# door_FM_rev_A.net
KiCad netlist of a schematic drawn in EAGLE
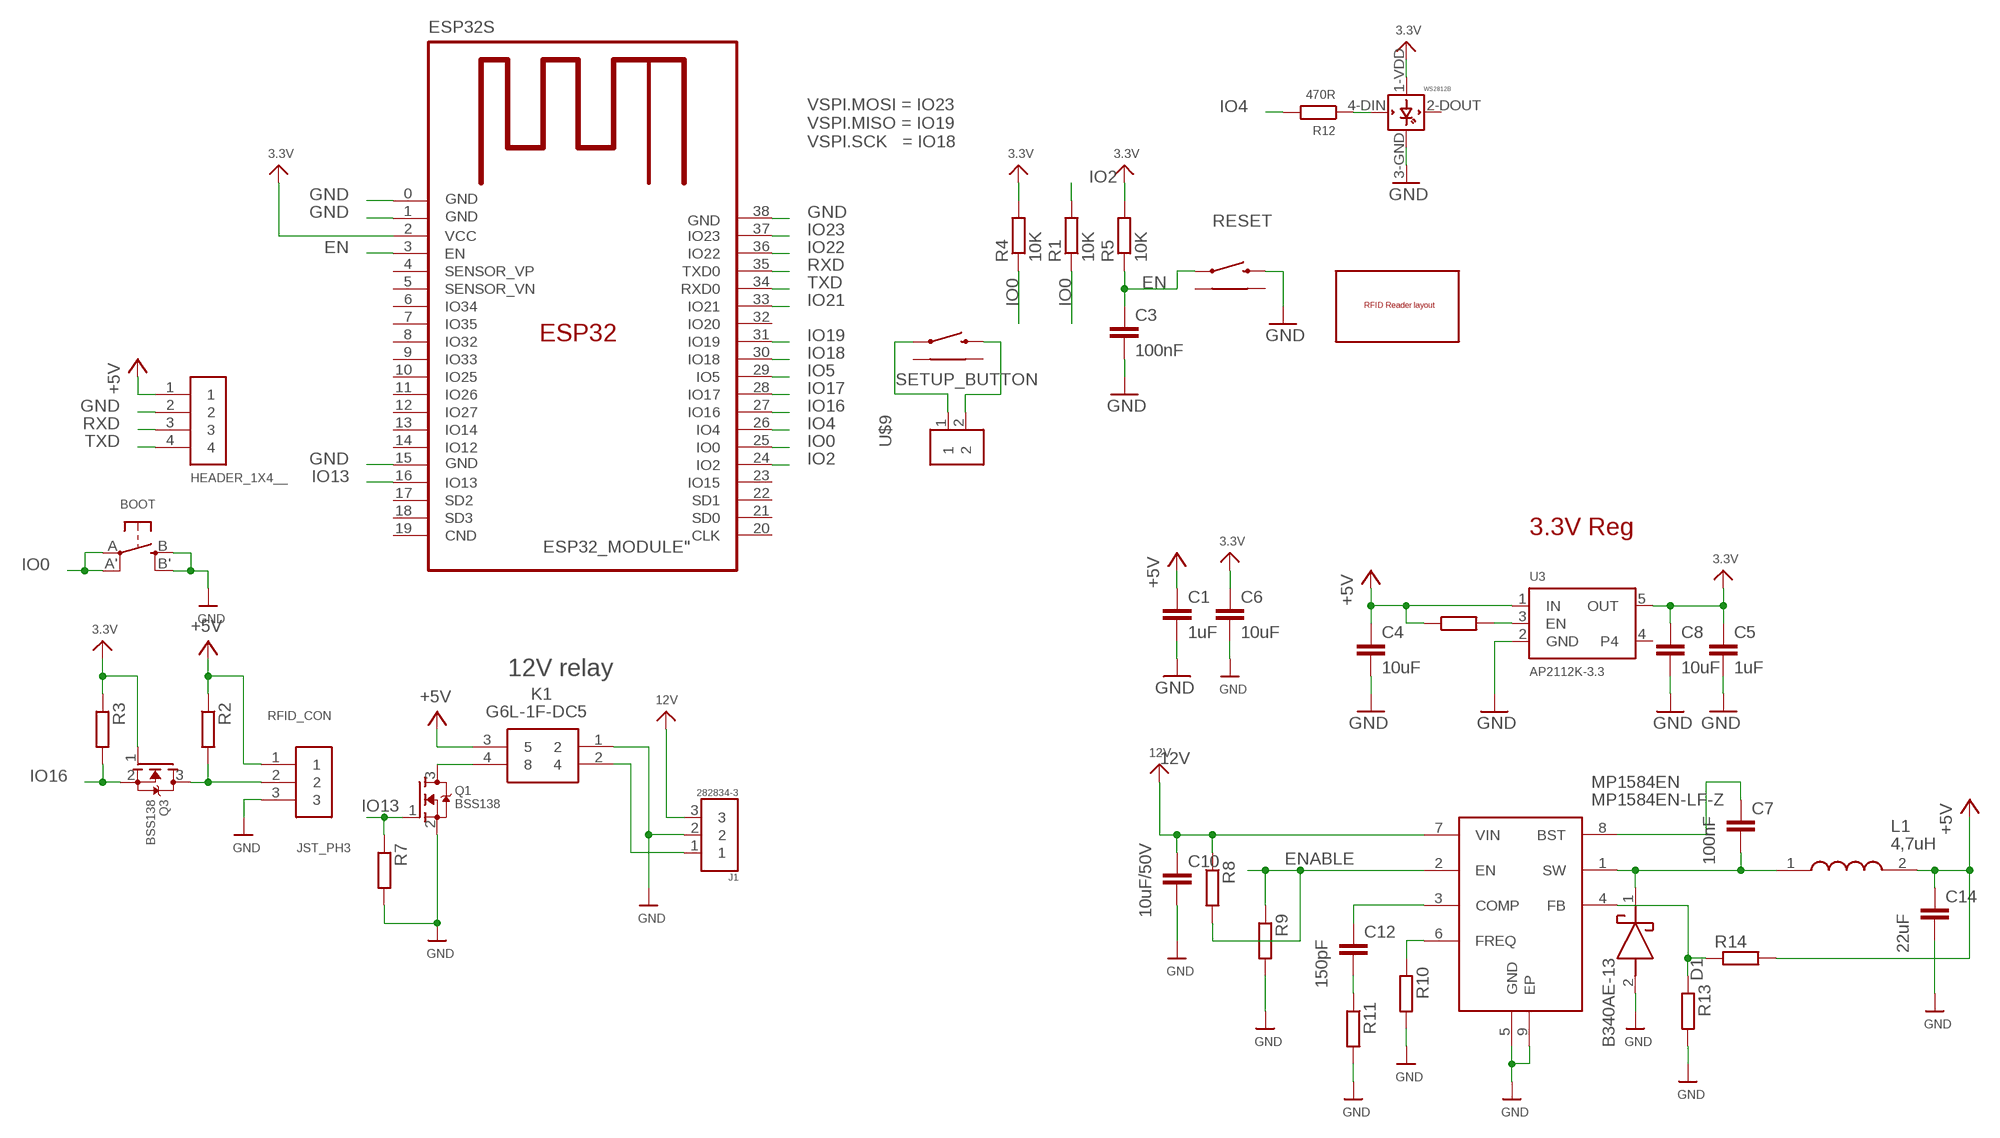
[diagram p0: schematic, sheet 1]

(export (version "E")
  (design (tool "Eeschema 10.0.6"))
  (components
    (comp (ref "BOOT")
      (value "BUTTON_KMR2_4.6X2.8")
      (footprint "eagle-import:BUTTON_KMR2_4.6X2.8")
      (libsource (lib "eagle-import") (part "BUTTON_KMR2_4.6X2.8"))
    )
    (comp (ref "C1")
      (value "1uF")
      (footprint "eagle-import:C0805")
      (libsource (lib "eagle-import") (part "C-EUC0805"))
    )
    (comp (ref "C3")
      (value "100nF")
      (footprint "eagle-import:C0805")
      (libsource (lib "eagle-import") (part "C-EUC0805"))
    )
    (comp (ref "C4")
      (value "10uF")
      (footprint "eagle-import:C0805")
      (libsource (lib "eagle-import") (part "C-EUC0805"))
    )
    (comp (ref "C5")
      (value "1uF")
      (footprint "eagle-import:C0805")
      (libsource (lib "eagle-import") (part "C-EUC0805"))
    )
    (comp (ref "C6")
      (value "10uF")
      (footprint "eagle-import:C0805")
      (libsource (lib "eagle-import") (part "C-EUC0805"))
    )
    (comp (ref "C7")
      (value "100nF")
      (footprint "eagle-import:C0805")
      (libsource (lib "eagle-import") (part "C-EUC0805"))
    )
    (comp (ref "C8")
      (value "10uF")
      (footprint "eagle-import:C0805")
      (libsource (lib "eagle-import") (part "C-EUC0805"))
    )
    (comp (ref "C10")
      (value "10uF/50V")
      (footprint "eagle-import:C0805")
      (libsource (lib "eagle-import") (part "C-EUC0805"))
    )
    (comp (ref "C12")
      (value "150pF")
      (footprint "eagle-import:C0805")
      (libsource (lib "eagle-import") (part "C-EUC0805"))
    )
    (comp (ref "C14")
      (value "22uF")
      (footprint "eagle-import:C0805")
      (libsource (lib "eagle-import") (part "C-EUC0805"))
    )
    (comp (ref "CN1")
      (value "HEADER_1X4__")
      (footprint "eagle-import:HEADER_1X4_RIGHT_ANGLE")
      (libsource (lib "eagle-import") (part "HEADER_1X4__"))
    )
    (comp (ref "D1")
      (value "B340AE-13")
      (footprint "eagle-import:DIOM5226X240N")
      (fields (field (name "MOUSER_PART_NUMBER") "621-B340AE-13"))
      (libsource (lib "eagle-import") (part "B340AE-13"))
    )
    (comp (ref "ESP32S")
      (value "ESP32_MODULE\"")
      (footprint "eagle-import:ESP32_MODULE")
      (libsource (lib "eagle-import") (part "ESP32_MODULE{dblquote}"))
    )
    (comp (ref "J1")
      (value "282834-3")
      (footprint "eagle-import:TE_282834-3")
      (fields (field (name "MF") "TE Connectivity"))
      (libsource (lib "eagle-import") (part "282834-3"))
    )
    (comp (ref "K1")
      (value "G6L-1F-DC5")
      (footprint "eagle-import:G6L-1F-DC5")
      (fields (field (name "MOUSER_PART_NUMBER") "653-G6L-1F-DC5"))
      (libsource (lib "eagle-import") (part "G6L-1F-DC5"))
    )
    (comp (ref "L1")
      (value "4,7uH")
      (footprint "eagle-import:ASPI-0630LR")
      (fields
        (field (name "MANUFACTURER_PART_NUMBER") "ASPI-0630LR-4R7M-T15")
        (field (name "MOUSER_PART_NUMBER") "815-ASPI0630LR4R7T15")
      )
      (libsource (lib "eagle-import") (part "ASPI-0630LR-4R7M-T15"))
    )
    (comp (ref "MP1584EN")
      (value "MP1584EN-LF-Z")
      (footprint "eagle-import:SOIC127P600X170-9N")
      (fields (field (name "MOUSER_PART_NUMBER") "946-MP1584ENLFZ"))
      (libsource (lib "eagle-import") (part "MP1584EN-LF-Z"))
    )
    (comp (ref "Q1")
      (value "BSS138")
      (footprint "eagle-import:SOT95P240X110-3")
      (libsource (lib "eagle-import") (part "MOSFET_N_"))
    )
    (comp (ref "Q3")
      (value "BSS138")
      (footprint "eagle-import:SOT95P240X110-3")
      (libsource (lib "eagle-import") (part "MOSFET_N_"))
    )
    (comp (ref "R1")
      (value "10K")
      (footprint "eagle-import:R0805")
      (libsource (lib "eagle-import") (part "R-EU_R0805"))
    )
    (comp (ref "R2")
      (value "10K")
      (footprint "eagle-import:R0805")
      (libsource (lib "eagle-import") (part "R-EU_R0805"))
    )
    (comp (ref "R3")
      (value "10K")
      (footprint "eagle-import:R0805")
      (libsource (lib "eagle-import") (part "R-EU_R0805"))
    )
    (comp (ref "R4")
      (value "10K")
      (footprint "eagle-import:R0805")
      (libsource (lib "eagle-import") (part "R-EU_R0805"))
    )
    (comp (ref "R5")
      (value "10K")
      (footprint "eagle-import:R0805")
      (libsource (lib "eagle-import") (part "R-EU_R0805"))
    )
    (comp (ref "R7")
      (value "10K")
      (footprint "eagle-import:R0805")
      (libsource (lib "eagle-import") (part "R-EU_R0805"))
    )
    (comp (ref "R8")
      (value "100K")
      (footprint "eagle-import:R0805")
      (libsource (lib "eagle-import") (part "R-EU_R0805"))
    )
    (comp (ref "R9")
      (value "24,9K")
      (footprint "eagle-import:R0805")
      (libsource (lib "eagle-import") (part "R-EU_R0805"))
    )
    (comp (ref "R10")
      (value "100K")
      (footprint "eagle-import:R0805")
      (libsource (lib "eagle-import") (part "R-EU_R0805"))
    )
    (comp (ref "R11")
      (value "100K")
      (footprint "eagle-import:R0805")
      (libsource (lib "eagle-import") (part "R-EU_R0805"))
    )
    (comp (ref "R12")
      (value "470R")
      (footprint "eagle-import:R0805")
      (libsource (lib "eagle-import") (part "R-EU_R0805"))
    )
    (comp (ref "R13")
      (value "40,2K")
      (footprint "eagle-import:R0805")
      (libsource (lib "eagle-import") (part "R-EU_R0805"))
    )
    (comp (ref "R14")
      (value "210K")
      (footprint "eagle-import:R0805")
      (libsource (lib "eagle-import") (part "R-EU_R0805"))
    )
    (comp (ref "R19")
      (value "10K")
      (footprint "eagle-import:R0805")
      (libsource (lib "eagle-import") (part "R-EU_R0805"))
    )
    (comp (ref "RESET")
      (value "TACTILE_SWITCH_RIGHT_ANGLE_THT_")
      (footprint "eagle-import:TACTILE_SWITCH_RIGHT_ANGLE_THT")
      (libsource (lib "eagle-import") (part "TACTILE_SWITCH_RIGHT_ANGLE_THT_"))
    )
    (comp (ref "RFID_CON")
      (value "JST_PH3")
      (footprint "eagle-import:JST-PH3")
      (libsource (lib "eagle-import") (part "JST_PH3"))
    )
    (comp (ref "SETUP_BUTTON")
      (value "TACTILE_SWITCH_RIGHT_ANGLE_THT_")
      (footprint "eagle-import:TACTILE_SWITCH_RIGHT_ANGLE_THT")
      (libsource (lib "eagle-import") (part "TACTILE_SWITCH_RIGHT_ANGLE_THT_"))
    )
    (comp (ref "U$9")
      (value "282834-2")
      (footprint "eagle-import:CONN_282834-2")
      (fields (field (name "MF") "TE Connectivity"))
      (libsource (lib "eagle-import") (part "282834-2"))
    )
    (comp (ref "U$10")
      (value "RFID_READER")
      (footprint "eagle-import:RFID_READER")
      (libsource (lib "eagle-import") (part "RFID_READER"))
    )
    (comp (ref "U3")
      (value "AP2112K-3.3")
      (footprint "eagle-import:SOT95P290X120-5")
      (libsource (lib "eagle-import") (part "AP2112K-3.3_"))
    )
    (comp (ref "WS2812B")
      (value "WS2812B__")
      (footprint "eagle-import:WS2812B_5050")
      (libsource (lib "eagle-import") (part "WS2812B__"))
    )
  )
  (nets
    (net (code "1") (name "+5V") (class "Default")
      (node (ref "C1") (pin "1") (pinfunction "1_1") (pintype "passive"))
      (node (ref "C14") (pin "1") (pinfunction "1_1") (pintype "passive"))
      (node (ref "C4") (pin "1") (pinfunction "1_1") (pintype "passive"))
      (node (ref "CN1") (pin "1") (pinfunction "1_1") (pintype "bidirectional"))
      (node (ref "K1") (pin "3") (pinfunction "5_3") (pintype "bidirectional"))
      (node (ref "L1") (pin "2") (pinfunction "2_2") (pintype "bidirectional"))
      (node (ref "R14") (pin "2") (pinfunction "2_2") (pintype "passive"))
      (node (ref "R19") (pin "1") (pinfunction "1_1") (pintype "passive"))
      (node (ref "R2") (pin "1") (pinfunction "1_1") (pintype "passive"))
      (node (ref "RFID_CON") (pin "1") (pinfunction "1_1") (pintype "bidirectional"))
      (node (ref "U3") (pin "1") (pinfunction "IN_1") (pintype "bidirectional"))
    )
    (net (code "2") (name "/EN") (class "Default")
      (node (ref "C3") (pin "1") (pinfunction "1_1") (pintype "passive"))
      (node (ref "ESP32S") (pin "3") (pinfunction "EN_3") (pintype "bidirectional"))
      (node (ref "R5") (pin "1") (pinfunction "1_1") (pintype "passive"))
      (node (ref "RESET") (pin "1") (pinfunction "1_1") (pintype "passive"))
    )
    (net (code "3") (name "/ENABLE") (class "Default")
      (node (ref "MP1584EN") (pin "2") (pinfunction "EN_2") (pintype "input"))
      (node (ref "R8") (pin "2") (pinfunction "2_2") (pintype "passive"))
      (node (ref "R9") (pin "1") (pinfunction "1_1") (pintype "passive"))
    )
    (net (code "4") (name "/IO0") (class "Default")
      (node (ref "BOOT") (pin "A") (pinfunction "P_A") (pintype "passive"))
      (node (ref "BOOT") (pin "A'") (pinfunction "P1_A'") (pintype "passive"))
      (node (ref "ESP32S") (pin "25") (pinfunction "IO0_25") (pintype "bidirectional"))
      (node (ref "R1") (pin "1") (pinfunction "1_1") (pintype "passive"))
      (node (ref "R4") (pin "1") (pinfunction "1_1") (pintype "passive"))
    )
    (net (code "5") (name "/IO2") (class "Default")
      (node (ref "ESP32S") (pin "24") (pinfunction "IO2_24") (pintype "bidirectional"))
      (node (ref "R1") (pin "2") (pinfunction "2_2") (pintype "passive"))
    )
    (net (code "6") (name "/IO4") (class "Default")
      (node (ref "ESP32S") (pin "26") (pinfunction "IO4_26") (pintype "bidirectional"))
      (node (ref "R12") (pin "2") (pinfunction "2_2") (pintype "passive"))
    )
    (net (code "7") (name "/IO5") (class "Default")
      (node (ref "ESP32S") (pin "29") (pinfunction "IO5_29") (pintype "bidirectional"))
    )
    (net (code "8") (name "/IO13") (class "Default")
      (node (ref "ESP32S") (pin "16") (pinfunction "IO13_16") (pintype "bidirectional"))
      (node (ref "Q1") (pin "1") (pinfunction "G_1") (pintype "bidirectional"))
      (node (ref "R7") (pin "1") (pinfunction "1_1") (pintype "passive"))
    )
    (net (code "9") (name "/IO16") (class "Default")
      (node (ref "ESP32S") (pin "27") (pinfunction "IO16_27") (pintype "bidirectional"))
      (node (ref "Q3") (pin "2") (pinfunction "S_2") (pintype "bidirectional"))
      (node (ref "R3") (pin "2") (pinfunction "2_2") (pintype "passive"))
    )
    (net (code "10") (name "/IO17") (class "Default")
      (node (ref "ESP32S") (pin "28") (pinfunction "IO17_28") (pintype "bidirectional"))
    )
    (net (code "11") (name "/IO18") (class "Default")
      (node (ref "ESP32S") (pin "30") (pinfunction "IO18_30") (pintype "bidirectional"))
    )
    (net (code "12") (name "/IO19") (class "Default")
      (node (ref "ESP32S") (pin "31") (pinfunction "IO19_31") (pintype "bidirectional"))
    )
    (net (code "13") (name "/IO21") (class "Default")
      (node (ref "ESP32S") (pin "33") (pinfunction "IO21_33") (pintype "bidirectional"))
    )
    (net (code "14") (name "/IO22") (class "Default")
      (node (ref "ESP32S") (pin "36") (pinfunction "IO22_36") (pintype "bidirectional"))
    )
    (net (code "15") (name "/IO23") (class "Default")
      (node (ref "ESP32S") (pin "37") (pinfunction "IO23_37") (pintype "bidirectional"))
    )
    (net (code "16") (name "/RXD") (class "Default")
      (node (ref "CN1") (pin "3") (pinfunction "3_3") (pintype "bidirectional"))
      (node (ref "ESP32S") (pin "35") (pinfunction "TXD0_35") (pintype "bidirectional"))
    )
    (net (code "17") (name "/TXD") (class "Default")
      (node (ref "CN1") (pin "4") (pinfunction "4_4") (pintype "bidirectional"))
      (node (ref "ESP32S") (pin "34") (pinfunction "RXD0_34") (pintype "bidirectional"))
    )
    (net (code "18") (name "3.3V") (class "Default")
      (node (ref "C5") (pin "1") (pinfunction "1_1") (pintype "passive"))
      (node (ref "C6") (pin "1") (pinfunction "1_1") (pintype "passive"))
      (node (ref "C8") (pin "1") (pinfunction "1_1") (pintype "passive"))
      (node (ref "ESP32S") (pin "2") (pinfunction "VCC_2") (pintype "power_in"))
      (node (ref "Q3") (pin "1") (pinfunction "G_1") (pintype "bidirectional"))
      (node (ref "R3") (pin "1") (pinfunction "1_1") (pintype "passive"))
      (node (ref "R4") (pin "2") (pinfunction "2_2") (pintype "passive"))
      (node (ref "R5") (pin "2") (pinfunction "2_2") (pintype "passive"))
      (node (ref "U3") (pin "5") (pinfunction "OUT_5") (pintype "bidirectional"))
      (node (ref "WS2812B") (pin "1-VDD") (pinfunction "VDD_1-VDD") (pintype "bidirectional"))
    )
    (net (code "19") (name "12V") (class "Default")
      (node (ref "C10") (pin "1") (pinfunction "1_1") (pintype "passive"))
      (node (ref "J1") (pin "3") (pinfunction "3_3") (pintype "passive"))
      (node (ref "MP1584EN") (pin "7") (pinfunction "VIN_7") (pintype "power_in"))
      (node (ref "R8") (pin "1") (pinfunction "1_1") (pintype "passive"))
    )
    (net (code "20") (name "GND") (class "Default")
      (node (ref "BOOT") (pin "B") (pinfunction "S_B") (pintype "passive"))
      (node (ref "BOOT") (pin "B'") (pinfunction "S1_B'") (pintype "passive"))
      (node (ref "C1") (pin "2") (pinfunction "2_2") (pintype "passive"))
      (node (ref "C10") (pin "2") (pinfunction "2_2") (pintype "passive"))
      (node (ref "C14") (pin "2") (pinfunction "2_2") (pintype "passive"))
      (node (ref "C3") (pin "2") (pinfunction "2_2") (pintype "passive"))
      (node (ref "C4") (pin "2") (pinfunction "2_2") (pintype "passive"))
      (node (ref "C5") (pin "2") (pinfunction "2_2") (pintype "passive"))
      (node (ref "C6") (pin "2") (pinfunction "2_2") (pintype "passive"))
      (node (ref "C8") (pin "2") (pinfunction "2_2") (pintype "passive"))
      (node (ref "CN1") (pin "2") (pinfunction "2_2") (pintype "bidirectional"))
      (node (ref "D1") (pin "2") (pinfunction "A_2") (pintype "bidirectional"))
      (node (ref "ESP32S") (pin "0") (pinfunction "GND_0") (pintype "power_in"))
      (node (ref "ESP32S") (pin "1") (pinfunction "GND_1") (pintype "power_in"))
      (node (ref "ESP32S") (pin "15") (pinfunction "GND_15") (pintype "power_in"))
      (node (ref "ESP32S") (pin "38") (pinfunction "GND_38") (pintype "power_in"))
      (node (ref "J1") (pin "2") (pinfunction "2_2") (pintype "passive"))
      (node (ref "K1") (pin "1") (pinfunction "2_1") (pintype "bidirectional"))
      (node (ref "MP1584EN") (pin "5") (pinfunction "GND_5") (pintype "power_in"))
      (node (ref "MP1584EN") (pin "9") (pinfunction "EP_9") (pintype "bidirectional"))
      (node (ref "Q1") (pin "2") (pinfunction "S_2") (pintype "bidirectional"))
      (node (ref "R10") (pin "2") (pinfunction "2_2") (pintype "passive"))
      (node (ref "R11") (pin "2") (pinfunction "2_2") (pintype "passive"))
      (node (ref "R13") (pin "2") (pinfunction "2_2") (pintype "passive"))
      (node (ref "R7") (pin "2") (pinfunction "2_2") (pintype "passive"))
      (node (ref "R9") (pin "2") (pinfunction "2_2") (pintype "passive"))
      (node (ref "RESET") (pin "2") (pinfunction "2_2") (pintype "passive"))
      (node (ref "RFID_CON") (pin "3") (pinfunction "3_3") (pintype "bidirectional"))
      (node (ref "U3") (pin "2") (pinfunction "GND_2") (pintype "bidirectional"))
      (node (ref "WS2812B") (pin "3-GND") (pinfunction "GND_3-GND") (pintype "bidirectional"))
    )
    (net (code "21") (name "Net-(C12-Pad2)") (class "Default")
      (node (ref "C12") (pin "2") (pinfunction "2_2") (pintype "passive"))
      (node (ref "R11") (pin "1") (pinfunction "1_1") (pintype "passive"))
    )
    (net (code "22") (name "Net-(D1-K)") (class "Default")
      (node (ref "C7") (pin "2") (pinfunction "2_2") (pintype "passive"))
      (node (ref "D1") (pin "1") (pinfunction "K_1") (pintype "bidirectional"))
      (node (ref "L1") (pin "1") (pinfunction "1_1") (pintype "bidirectional"))
      (node (ref "MP1584EN") (pin "1") (pinfunction "SW_1") (pintype "output"))
    )
    (net (code "23") (name "Net-(K1-4)") (class "Default")
      (node (ref "J1") (pin "1") (pinfunction "1_1") (pintype "passive"))
      (node (ref "K1") (pin "2") (pinfunction "4_2") (pintype "bidirectional"))
    )
    (net (code "24") (name "Net-(K1-8)") (class "Default")
      (node (ref "K1") (pin "4") (pinfunction "8_4") (pintype "bidirectional"))
      (node (ref "Q1") (pin "3") (pinfunction "D_3") (pintype "bidirectional"))
    )
    (net (code "25") (name "Net-(MP1584EN-BST)") (class "Default")
      (node (ref "C7") (pin "1") (pinfunction "1_1") (pintype "passive"))
      (node (ref "MP1584EN") (pin "8") (pinfunction "BST_8") (pintype "input"))
    )
    (net (code "26") (name "Net-(MP1584EN-COMP)") (class "Default")
      (node (ref "C12") (pin "1") (pinfunction "1_1") (pintype "passive"))
      (node (ref "MP1584EN") (pin "3") (pinfunction "COMP_3") (pintype "bidirectional"))
    )
    (net (code "27") (name "Net-(MP1584EN-FB)") (class "Default")
      (node (ref "MP1584EN") (pin "4") (pinfunction "FB_4") (pintype "input"))
      (node (ref "R13") (pin "1") (pinfunction "1_1") (pintype "passive"))
      (node (ref "R14") (pin "1") (pinfunction "1_1") (pintype "passive"))
    )
    (net (code "28") (name "Net-(MP1584EN-FREQ)") (class "Default")
      (node (ref "MP1584EN") (pin "6") (pinfunction "FREQ_6") (pintype "input"))
      (node (ref "R10") (pin "1") (pinfunction "1_1") (pintype "passive"))
    )
    (net (code "29") (name "Net-(Q3-D)") (class "Default")
      (node (ref "Q3") (pin "3") (pinfunction "D_3") (pintype "bidirectional"))
      (node (ref "R2") (pin "2") (pinfunction "2_2") (pintype "passive"))
      (node (ref "RFID_CON") (pin "2") (pinfunction "2_2") (pintype "bidirectional"))
    )
    (net (code "30") (name "Net-(SETUP_BUTTON-Pad1)") (class "Default")
      (node (ref "SETUP_BUTTON") (pin "1") (pinfunction "1_1") (pintype "passive"))
      (node (ref "U$9") (pin "1") (pinfunction "1_1") (pintype "passive"))
    )
    (net (code "31") (name "Net-(SETUP_BUTTON-Pad2)") (class "Default")
      (node (ref "SETUP_BUTTON") (pin "2") (pinfunction "2_2") (pintype "passive"))
      (node (ref "U$9") (pin "2") (pinfunction "2_2") (pintype "passive"))
    )
    (net (code "32") (name "Net-(U3-EN)") (class "Default")
      (node (ref "R19") (pin "2") (pinfunction "2_2") (pintype "passive"))
      (node (ref "U3") (pin "3") (pinfunction "EN_3") (pintype "bidirectional"))
    )
    (net (code "33") (name "Net-(WS2812B-DIN)") (class "Default")
      (node (ref "R12") (pin "1") (pinfunction "1_1") (pintype "passive"))
      (node (ref "WS2812B") (pin "4-DIN") (pinfunction "DIN_4-DIN") (pintype "input"))
    )
    (net (code "34") (name "unconnected-(ESP32S-CLK-Pad20)") (class "Default")
      (node (ref "ESP32S") (pin "20") (pinfunction "CLK_20") (pintype "bidirectional"))
    )
    (net (code "35") (name "unconnected-(ESP32S-CND-Pad19)") (class "Default")
      (node (ref "ESP32S") (pin "19") (pinfunction "CND_19") (pintype "bidirectional"))
    )
    (net (code "36") (name "unconnected-(ESP32S-IO12-Pad14)") (class "Default")
      (node (ref "ESP32S") (pin "14") (pinfunction "IO12_14") (pintype "bidirectional"))
    )
    (net (code "37") (name "unconnected-(ESP32S-IO14-Pad13)") (class "Default")
      (node (ref "ESP32S") (pin "13") (pinfunction "IO14_13") (pintype "bidirectional"))
    )
    (net (code "38") (name "unconnected-(ESP32S-IO15-Pad23)") (class "Default")
      (node (ref "ESP32S") (pin "23") (pinfunction "IO15_23") (pintype "bidirectional"))
    )
    (net (code "39") (name "unconnected-(ESP32S-IO20-Pad32)") (class "Default")
      (node (ref "ESP32S") (pin "32") (pinfunction "IO20_32") (pintype "bidirectional"))
    )
    (net (code "40") (name "unconnected-(ESP32S-IO25-Pad10)") (class "Default")
      (node (ref "ESP32S") (pin "10") (pinfunction "IO25_10") (pintype "bidirectional"))
    )
    (net (code "41") (name "unconnected-(ESP32S-IO26-Pad11)") (class "Default")
      (node (ref "ESP32S") (pin "11") (pinfunction "IO26_11") (pintype "bidirectional"))
    )
    (net (code "42") (name "unconnected-(ESP32S-IO27-Pad12)") (class "Default")
      (node (ref "ESP32S") (pin "12") (pinfunction "IO27_12") (pintype "bidirectional"))
    )
    (net (code "43") (name "unconnected-(ESP32S-IO32-Pad8)") (class "Default")
      (node (ref "ESP32S") (pin "8") (pinfunction "IO32_8") (pintype "bidirectional"))
    )
    (net (code "44") (name "unconnected-(ESP32S-IO33-Pad9)") (class "Default")
      (node (ref "ESP32S") (pin "9") (pinfunction "IO33_9") (pintype "bidirectional"))
    )
    (net (code "45") (name "unconnected-(ESP32S-IO34-Pad6)") (class "Default")
      (node (ref "ESP32S") (pin "6") (pinfunction "IO34_6") (pintype "bidirectional"))
    )
    (net (code "46") (name "unconnected-(ESP32S-IO35-Pad7)") (class "Default")
      (node (ref "ESP32S") (pin "7") (pinfunction "IO35_7") (pintype "bidirectional"))
    )
    (net (code "47") (name "unconnected-(ESP32S-SD0-Pad21)") (class "Default")
      (node (ref "ESP32S") (pin "21") (pinfunction "SD0_21") (pintype "bidirectional"))
    )
    (net (code "48") (name "unconnected-(ESP32S-SD1-Pad22)") (class "Default")
      (node (ref "ESP32S") (pin "22") (pinfunction "SD1_22") (pintype "bidirectional"))
    )
    (net (code "49") (name "unconnected-(ESP32S-SD2-Pad17)") (class "Default")
      (node (ref "ESP32S") (pin "17") (pinfunction "SD2_17") (pintype "bidirectional"))
    )
    (net (code "50") (name "unconnected-(ESP32S-SD3-Pad18)") (class "Default")
      (node (ref "ESP32S") (pin "18") (pinfunction "SD3_18") (pintype "bidirectional"))
    )
    (net (code "51") (name "unconnected-(ESP32S-SENSOR_VN-Pad5)") (class "Default")
      (node (ref "ESP32S") (pin "5") (pinfunction "SENSOR_VN_5") (pintype "bidirectional"))
    )
    (net (code "52") (name "unconnected-(ESP32S-SENSOR_VP-Pad4)") (class "Default")
      (node (ref "ESP32S") (pin "4") (pinfunction "SENSOR_VP_4") (pintype "bidirectional"))
    )
    (net (code "53") (name "unconnected-(RESET-3-PadANCHOR1)") (class "Default")
      (node (ref "RESET") (pin "ANCHOR1") (pinfunction "3_ANCHOR1") (pintype "passive"))
    )
    (net (code "54") (name "unconnected-(RESET-4-PadANCHOR2)") (class "Default")
      (node (ref "RESET") (pin "ANCHOR2") (pinfunction "4_ANCHOR2") (pintype "passive"))
    )
    (net (code "55") (name "unconnected-(SETUP_BUTTON-3-PadANCHOR1)") (class "Default")
      (node (ref "SETUP_BUTTON") (pin "ANCHOR1") (pinfunction "3_ANCHOR1") (pintype "passive"))
    )
    (net (code "56") (name "unconnected-(SETUP_BUTTON-4-PadANCHOR2)") (class "Default")
      (node (ref "SETUP_BUTTON") (pin "ANCHOR2") (pinfunction "4_ANCHOR2") (pintype "passive"))
    )
    (net (code "57") (name "unconnected-(U3-P4-Pad4)") (class "Default")
      (node (ref "U3") (pin "4") (pinfunction "P4_4") (pintype "bidirectional"))
    )
    (net (code "58") (name "unconnected-(WS2812B-DOUT-Pad2-DOUT)") (class "Default")
      (node (ref "WS2812B") (pin "2-DOUT") (pinfunction "DOUT_2-DOUT") (pintype "output"))
    )
  )
)
